# thermo_board.net
KiCad netlist of a schematic drawn in EAGLE
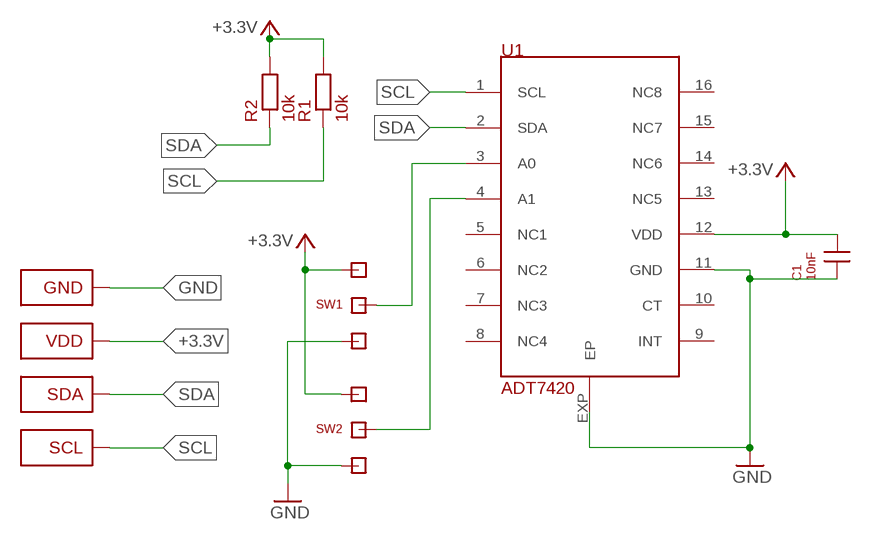
[diagram p0: schematic, sheet 1]

(export (version "E")
  (design (tool "Eeschema 10.0.6"))
  (components
    (comp (ref "C1")
      (value "10nF")
      (footprint "eagle-import:R0402")
      (libsource (lib "eagle-import") (part "CAPACITOR_CERAMIC_0402"))
    )
    (comp (ref "GND")
      (value "CONN_PAD_SQUARE")
      (footprint "eagle-import:CONN_PAD_SQUARE")
      (libsource (lib "eagle-import") (part "CONN_PAD_SQUARE"))
    )
    (comp (ref "R1")
      (value "10k")
      (footprint "eagle-import:R0402")
      (libsource (lib "eagle-import") (part "R_0402"))
    )
    (comp (ref "R2")
      (value "10k")
      (footprint "eagle-import:R0402")
      (libsource (lib "eagle-import") (part "R_0402"))
    )
    (comp (ref "SCL")
      (value "CONN_PAD_ROUND")
      (footprint "eagle-import:CONN_PAD_ROUND")
      (libsource (lib "eagle-import") (part "CONN_PAD_ROUND"))
    )
    (comp (ref "SDA")
      (value "CONN_PAD_ROUND")
      (footprint "eagle-import:CONN_PAD_ROUND")
      (libsource (lib "eagle-import") (part "CONN_PAD_ROUND"))
    )
    (comp (ref "SW1")
      (value "SOLDER_SWITCH_TWO")
      (footprint "eagle-import:SOLDER_SWITCH")
      (libsource (lib "eagle-import") (part "SOLDER_SWITCH_TWO"))
    )
    (comp (ref "SW2")
      (value "SOLDER_SWITCH_TWO")
      (footprint "eagle-import:SOLDER_SWITCH")
      (libsource (lib "eagle-import") (part "SOLDER_SWITCH_TWO"))
    )
    (comp (ref "U1")
      (value "ADT7420")
      (footprint "eagle-import:LFCSP16")
      (libsource (lib "eagle-import") (part "ADT7420"))
    )
    (comp (ref "VDD")
      (value "CONN_PAD_ROUND")
      (footprint "eagle-import:CONN_PAD_ROUND")
      (libsource (lib "eagle-import") (part "CONN_PAD_ROUND"))
    )
  )
  (nets
    (net (code "1") (name "+3.3V") (class "Default")
      (node (ref "C1") (pin "2") (pinfunction "P$2_2") (pintype "bidirectional"))
      (node (ref "R1") (pin "2") (pinfunction "P$2_2") (pintype "bidirectional"))
      (node (ref "R2") (pin "2") (pinfunction "P$2_2") (pintype "bidirectional"))
      (node (ref "SW1") (pin "1") (pinfunction "2_1") (pintype "bidirectional"))
      (node (ref "SW2") (pin "1") (pinfunction "2_1") (pintype "bidirectional"))
      (node (ref "U1") (pin "12") (pinfunction "VDD_12") (pintype "bidirectional"))
      (node (ref "VDD") (pin "P$1") (pinfunction "P$1_P$1") (pintype "bidirectional"))
    )
    (net (code "2") (name "GND") (class "Default")
      (node (ref "C1") (pin "1") (pinfunction "P$1_1") (pintype "bidirectional"))
      (node (ref "GND") (pin "P$1") (pinfunction "P$1_P$1") (pintype "bidirectional"))
      (node (ref "SW1") (pin "2") (pinfunction "1_2") (pintype "bidirectional"))
      (node (ref "SW2") (pin "2") (pinfunction "1_2") (pintype "bidirectional"))
      (node (ref "U1") (pin "11") (pinfunction "GND_11") (pintype "bidirectional"))
      (node (ref "U1") (pin "EXP") (pinfunction "EP_EXP") (pintype "bidirectional"))
    )
    (net (code "3") (name "Net-(U1-A0)") (class "Default")
      (node (ref "SW1") (pin "MID") (pinfunction "MID_MID") (pintype "bidirectional"))
      (node (ref "U1") (pin "3") (pinfunction "A0_3") (pintype "bidirectional"))
    )
    (net (code "4") (name "Net-(U1-A1)") (class "Default")
      (node (ref "SW2") (pin "MID") (pinfunction "MID_MID") (pintype "bidirectional"))
      (node (ref "U1") (pin "4") (pinfunction "A1_4") (pintype "bidirectional"))
    )
    (net (code "5") (name "SCL") (class "Default")
      (node (ref "R1") (pin "1") (pinfunction "P$1_1") (pintype "bidirectional"))
      (node (ref "SCL") (pin "P$1") (pinfunction "P$1_P$1") (pintype "bidirectional"))
      (node (ref "U1") (pin "1") (pinfunction "SCL_1") (pintype "bidirectional"))
    )
    (net (code "6") (name "SDA") (class "Default")
      (node (ref "R2") (pin "1") (pinfunction "P$1_1") (pintype "bidirectional"))
      (node (ref "SDA") (pin "P$1") (pinfunction "P$1_P$1") (pintype "bidirectional"))
      (node (ref "U1") (pin "2") (pinfunction "SDA_2") (pintype "bidirectional"))
    )
    (net (code "7") (name "unconnected-(U1-CT-Pad10)") (class "Default")
      (node (ref "U1") (pin "10") (pinfunction "CT_10") (pintype "bidirectional"))
    )
    (net (code "8") (name "unconnected-(U1-INT-Pad9)") (class "Default")
      (node (ref "U1") (pin "9") (pinfunction "INT_9") (pintype "bidirectional"))
    )
    (net (code "9") (name "unconnected-(U1-NC1-Pad5)") (class "Default")
      (node (ref "U1") (pin "5") (pinfunction "NC1_5") (pintype "bidirectional"))
    )
    (net (code "10") (name "unconnected-(U1-NC2-Pad6)") (class "Default")
      (node (ref "U1") (pin "6") (pinfunction "NC2_6") (pintype "bidirectional"))
    )
    (net (code "11") (name "unconnected-(U1-NC3-Pad7)") (class "Default")
      (node (ref "U1") (pin "7") (pinfunction "NC3_7") (pintype "bidirectional"))
    )
    (net (code "12") (name "unconnected-(U1-NC4-Pad8)") (class "Default")
      (node (ref "U1") (pin "8") (pinfunction "NC4_8") (pintype "bidirectional"))
    )
    (net (code "13") (name "unconnected-(U1-NC5-Pad13)") (class "Default")
      (node (ref "U1") (pin "13") (pinfunction "NC5_13") (pintype "bidirectional"))
    )
    (net (code "14") (name "unconnected-(U1-NC6-Pad14)") (class "Default")
      (node (ref "U1") (pin "14") (pinfunction "NC6_14") (pintype "bidirectional"))
    )
    (net (code "15") (name "unconnected-(U1-NC7-Pad15)") (class "Default")
      (node (ref "U1") (pin "15") (pinfunction "NC7_15") (pintype "bidirectional"))
    )
    (net (code "16") (name "unconnected-(U1-NC8-Pad16)") (class "Default")
      (node (ref "U1") (pin "16") (pinfunction "NC8_16") (pintype "bidirectional"))
    )
  )
)
